# isolatedInput.net
KiCad netlist of a schematic drawn in Altium Designer
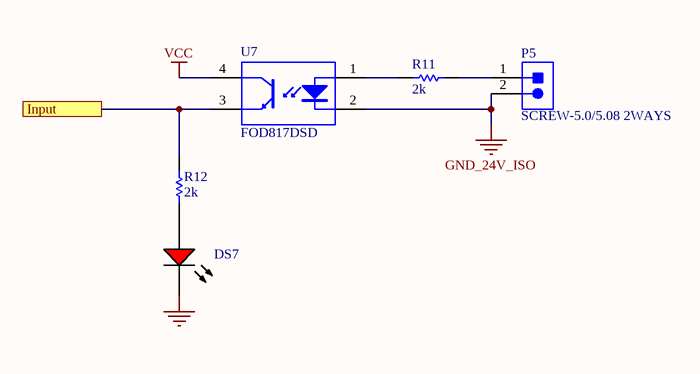
[diagram p0: isolatedInput.SchDoc]

(export (version "E")
  (design (tool "Eeschema 10.0.6"))
  (components
    (comp (ref "DS7")
      (value "TLMS1100-GS08")
      (footprint "VISH-TLMX1100_V")
      (description "LED, RED, 2.1 V, -40 to 100 degC, 2-Pin SMD (0603), RoHS, Tape and Reel")
      (fields (field (name "TOLERANCE") "5%"))
      (libsource (lib "Altium Content Vault") (part "LED-RED-AK-2"))
    )
    (comp (ref "P5")
      (value "SCREW-5.0/5.08 2WAYS")
      (footprint "SCREW-5.0-2WAYS_V")
      (description "Socket, Screw Terminal Block, 2 Way, 5.0 mm Pitch, 90 Degree Angle, Through-Hole")
      (fields (field (name "MANUFACTURER") "No Vendor"))
      (libsource (lib "Altium Content Vault") (part "SCREW-2WAYS"))
    )
    (comp (ref "R11")
      (value "2k")
      (footprint "RESC0805(2012)_L")
      (description "10K2 0.125W 1% 0805 (2012 Metric)  SMD")
      (fields (field (name "TOLERANCE") "1 %") (field (name "POWER") "0.125 W"))
      (libsource (lib "Altium Content Vault") (part "RES"))
    )
    (comp (ref "R12")
      (value "2k")
      (footprint "RESC0805(2012)_L")
      (description "10K2 0.125W 1% 0805 (2012 Metric)  SMD")
      (fields (field (name "TOLERANCE") "1 %") (field (name "POWER") "0.125 W"))
      (libsource (lib "Altium Content Vault") (part "RES"))
    )
    (comp (ref "U7")
      (value "FOD817DSD")
      (footprint "FAIR-MDIP-4_V")
      (fields (field (name "MANUFACTURER") "Fairchild Semiconductor"))
      (libsource (lib "Altium Content Vault") (part "OPTO-AKEC-4"))
    )
  )
  (nets
    (net (code "1") (name "/Input") (class "Default")
      (node (ref "R12") (pin "1") (pinfunction "1_1") (pintype "passive"))
      (node (ref "U7") (pin "3") (pinfunction "EMITTER_3") (pintype "passive"))
    )
    (net (code "2") (name "GND") (class "Default")
      (node (ref "DS7") (pin "2") (pinfunction "K_2") (pintype "passive"))
    )
    (net (code "3") (name "GND_24V_ISO") (class "Default")
      (node (ref "P5") (pin "2") (pinfunction "2_2") (pintype "passive"))
      (node (ref "U7") (pin "2") (pinfunction "CATHODE_2") (pintype "passive"))
    )
    (net (code "4") (name "Net-(DS7-A)") (class "Default")
      (node (ref "DS7") (pin "1") (pinfunction "A_1") (pintype "passive"))
      (node (ref "R12") (pin "2") (pinfunction "2_2") (pintype "passive"))
    )
    (net (code "5") (name "Net-(P5-Pad1)") (class "Default")
      (node (ref "P5") (pin "1") (pinfunction "1_1") (pintype "passive"))
      (node (ref "R11") (pin "1") (pinfunction "1_1") (pintype "passive"))
    )
    (net (code "6") (name "Net-(U7-ANODE)") (class "Default")
      (node (ref "R11") (pin "2") (pinfunction "2_2") (pintype "passive"))
      (node (ref "U7") (pin "1") (pinfunction "ANODE_1") (pintype "passive"))
    )
    (net (code "7") (name "VCC") (class "Default")
      (node (ref "U7") (pin "4") (pinfunction "COLLECTOR_4") (pintype "passive"))
    )
  )
)
